# hm10.net
KiCad netlist of a schematic drawn in Altium Designer
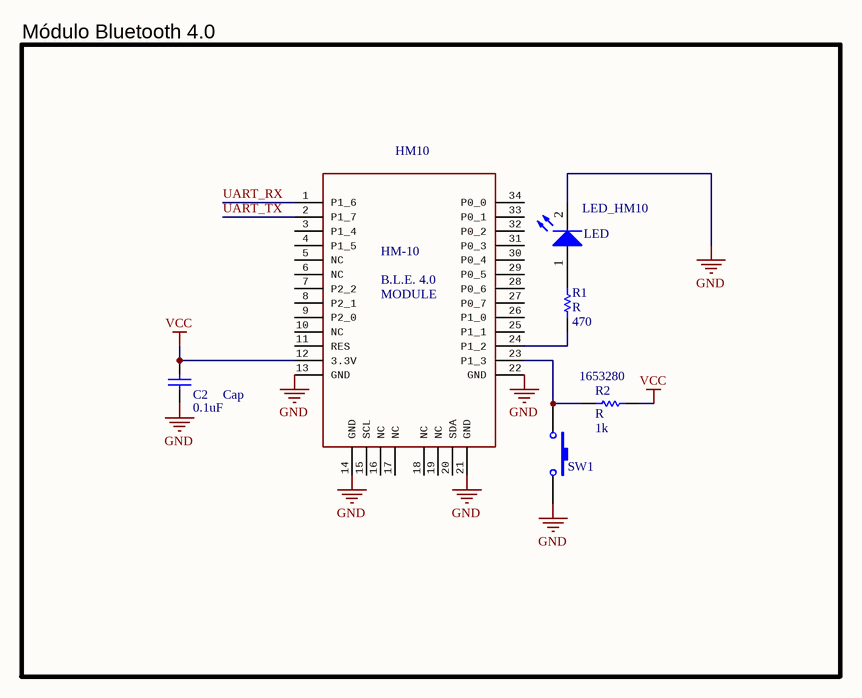
[diagram p0: hm10.SchDoc]

(export (version "E")
  (design (tool "Eeschema 10.0.6"))
  (components
    (comp (ref "C2")
      (value "Cap")
      (footprint "0805")
      (description "Capacitor")
      (fields (field (name "ALTIUM_VALUE") "0.1uF") (field (name "PUBLISHER") "Altium Limited"))
      (libsource (lib "Miscellaneous Devices") (part "Cap"))
    )
    (comp (ref "HM10")
      (value "HM-10 Module")
      (footprint "HM-10 module")
      (libsource (lib "B105lib") (part "HM-10 Module"))
    )
    (comp (ref "LED_HM10") (value "LED") (footprint "0603 LED-RED") (libsource (lib "B105lib") (part "LED")))
    (comp (ref "R1")
      (value "R")
      (footprint "0805 RES")
      (description "Resistor")
      (fields
        (field (name "MANUFACTURER") "Generic Components")
        (field (name "ALTIUM_VALUE") "470")
        (field (name "PUBLISHER") "Altium Hobart Technology Centre")
      )
      (libsource (lib "LSI") (part "R"))
    )
    (comp (ref "R2")
      (value "R")
      (footprint "0805 RES")
      (description "Resistor")
      (fields
        (field (name "MANUFACTURER") "Generic Components")
        (field (name "ALTIUM_VALUE") "1k")
        (field (name "SUPPLIER PART NUMBER 1") "1653280")
        (field (name "PUBLISHER") "Altium Hobart Technology Centre")
      )
      (libsource (lib "LSI") (part "R"))
    )
    (comp (ref "SW1")
      (value "Pulsador")
      (footprint "B3U-1000P")
      (description "Switch")
      (fields (field (name "MANUFACTURER") "Generic Components"))
      (libsource (lib "LSI") (part "Pulsador_1"))
    )
  )
  (nets
    (net (code "1") (name "/UART_RX") (class "Default")
      (node (ref "HM10") (pin "1") (pinfunction "P1_6_1") (pintype "passive"))
    )
    (net (code "2") (name "/UART_TX") (class "Default")
      (node (ref "HM10") (pin "2") (pinfunction "P1_7_2") (pintype "passive"))
    )
    (net (code "3") (name "GND") (class "Default")
      (node (ref "C2") (pin "1") (pinfunction "1_1") (pintype "passive"))
      (node (ref "HM10") (pin "13") (pinfunction "GND_13") (pintype "passive"))
      (node (ref "HM10") (pin "14") (pinfunction "GND_14") (pintype "passive"))
      (node (ref "HM10") (pin "21") (pinfunction "GND_21") (pintype "passive"))
      (node (ref "HM10") (pin "22") (pinfunction "GND_22") (pintype "passive"))
      (node (ref "LED_HM10") (pin "2") (pinfunction "C_2") (pintype "passive"))
      (node (ref "SW1") (pin "2") (pinfunction "2_2") (pintype "passive"))
    )
    (net (code "4") (name "Net-(HM10-P1_2)") (class "Default")
      (node (ref "HM10") (pin "24") (pinfunction "P1_2_24") (pintype "passive"))
      (node (ref "R1") (pin "2") (pinfunction "2_2") (pintype "passive"))
    )
    (net (code "5") (name "Net-(HM10-P1_3)") (class "Default")
      (node (ref "HM10") (pin "23") (pinfunction "P1_3_23") (pintype "passive"))
      (node (ref "R2") (pin "1") (pinfunction "1_1") (pintype "passive"))
      (node (ref "SW1") (pin "1") (pinfunction "1_1") (pintype "passive"))
    )
    (net (code "6") (name "Net-(LED_HM10-A)") (class "Default")
      (node (ref "LED_HM10") (pin "1") (pinfunction "A_1") (pintype "passive"))
      (node (ref "R1") (pin "1") (pinfunction "1_1") (pintype "passive"))
    )
    (net (code "7") (name "VCC") (class "Default")
      (node (ref "C2") (pin "2") (pinfunction "2_2") (pintype "passive"))
      (node (ref "HM10") (pin "12") (pinfunction "3.3V_12") (pintype "passive"))
      (node (ref "R2") (pin "2") (pinfunction "2_2") (pintype "passive"))
    )
    (net (code "8") (name "unconnected-(HM10-NC-Pad5)") (class "Default")
      (node (ref "HM10") (pin "5") (pinfunction "NC_5") (pintype "passive"))
    )
    (net (code "9") (name "unconnected-(HM10-NC-Pad6)") (class "Default")
      (node (ref "HM10") (pin "6") (pinfunction "NC_6") (pintype "passive"))
    )
    (net (code "10") (name "unconnected-(HM10-NC-Pad10)") (class "Default")
      (node (ref "HM10") (pin "10") (pinfunction "NC_10") (pintype "passive"))
    )
    (net (code "11") (name "unconnected-(HM10-NC-Pad16)") (class "Default")
      (node (ref "HM10") (pin "16") (pinfunction "NC_16") (pintype "passive"))
    )
    (net (code "12") (name "unconnected-(HM10-NC-Pad17)") (class "Default")
      (node (ref "HM10") (pin "17") (pinfunction "NC_17") (pintype "passive"))
    )
    (net (code "13") (name "unconnected-(HM10-NC-Pad18)") (class "Default")
      (node (ref "HM10") (pin "18") (pinfunction "NC_18") (pintype "passive"))
    )
    (net (code "14") (name "unconnected-(HM10-NC-Pad19)") (class "Default")
      (node (ref "HM10") (pin "19") (pinfunction "NC_19") (pintype "passive"))
    )
    (net (code "15") (name "unconnected-(HM10-P0_0-Pad34)") (class "Default")
      (node (ref "HM10") (pin "34") (pinfunction "P0_0_34") (pintype "passive"))
    )
    (net (code "16") (name "unconnected-(HM10-P0_1-Pad33)") (class "Default")
      (node (ref "HM10") (pin "33") (pinfunction "P0_1_33") (pintype "passive"))
    )
    (net (code "17") (name "unconnected-(HM10-P0_2-Pad32)") (class "Default")
      (node (ref "HM10") (pin "32") (pinfunction "P0_2_32") (pintype "passive"))
    )
    (net (code "18") (name "unconnected-(HM10-P0_3-Pad31)") (class "Default")
      (node (ref "HM10") (pin "31") (pinfunction "P0_3_31") (pintype "passive"))
    )
    (net (code "19") (name "unconnected-(HM10-P0_4-Pad30)") (class "Default")
      (node (ref "HM10") (pin "30") (pinfunction "P0_4_30") (pintype "passive"))
    )
    (net (code "20") (name "unconnected-(HM10-P0_5-Pad29)") (class "Default")
      (node (ref "HM10") (pin "29") (pinfunction "P0_5_29") (pintype "passive"))
    )
    (net (code "21") (name "unconnected-(HM10-P0_6-Pad28)") (class "Default")
      (node (ref "HM10") (pin "28") (pinfunction "P0_6_28") (pintype "passive"))
    )
    (net (code "22") (name "unconnected-(HM10-P0_7-Pad27)") (class "Default")
      (node (ref "HM10") (pin "27") (pinfunction "P0_7_27") (pintype "passive"))
    )
    (net (code "23") (name "unconnected-(HM10-P1_0-Pad26)") (class "Default")
      (node (ref "HM10") (pin "26") (pinfunction "P1_0_26") (pintype "passive"))
    )
    (net (code "24") (name "unconnected-(HM10-P1_1-Pad25)") (class "Default")
      (node (ref "HM10") (pin "25") (pinfunction "P1_1_25") (pintype "passive"))
    )
    (net (code "25") (name "unconnected-(HM10-P1_4-Pad3)") (class "Default")
      (node (ref "HM10") (pin "3") (pinfunction "P1_4_3") (pintype "passive"))
    )
    (net (code "26") (name "unconnected-(HM10-P1_5-Pad4)") (class "Default")
      (node (ref "HM10") (pin "4") (pinfunction "P1_5_4") (pintype "passive"))
    )
    (net (code "27") (name "unconnected-(HM10-P2_0-Pad9)") (class "Default")
      (node (ref "HM10") (pin "9") (pinfunction "P2_0_9") (pintype "passive"))
    )
    (net (code "28") (name "unconnected-(HM10-P2_1-Pad8)") (class "Default")
      (node (ref "HM10") (pin "8") (pinfunction "P2_1_8") (pintype "passive"))
    )
    (net (code "29") (name "unconnected-(HM10-P2_2-Pad7)") (class "Default")
      (node (ref "HM10") (pin "7") (pinfunction "P2_2_7") (pintype "passive"))
    )
    (net (code "30") (name "unconnected-(HM10-RES-Pad11)") (class "Default")
      (node (ref "HM10") (pin "11") (pinfunction "RES_11") (pintype "passive"))
    )
    (net (code "31") (name "unconnected-(HM10-SCL-Pad15)") (class "Default")
      (node (ref "HM10") (pin "15") (pinfunction "SCL_15") (pintype "passive"))
    )
    (net (code "32") (name "unconnected-(HM10-SDA-Pad20)") (class "Default")
      (node (ref "HM10") (pin "20") (pinfunction "SDA_20") (pintype "passive"))
    )
  )
)
